# bt_remote_controller.net
KiCad netlist of a schematic drawn in EAGLE
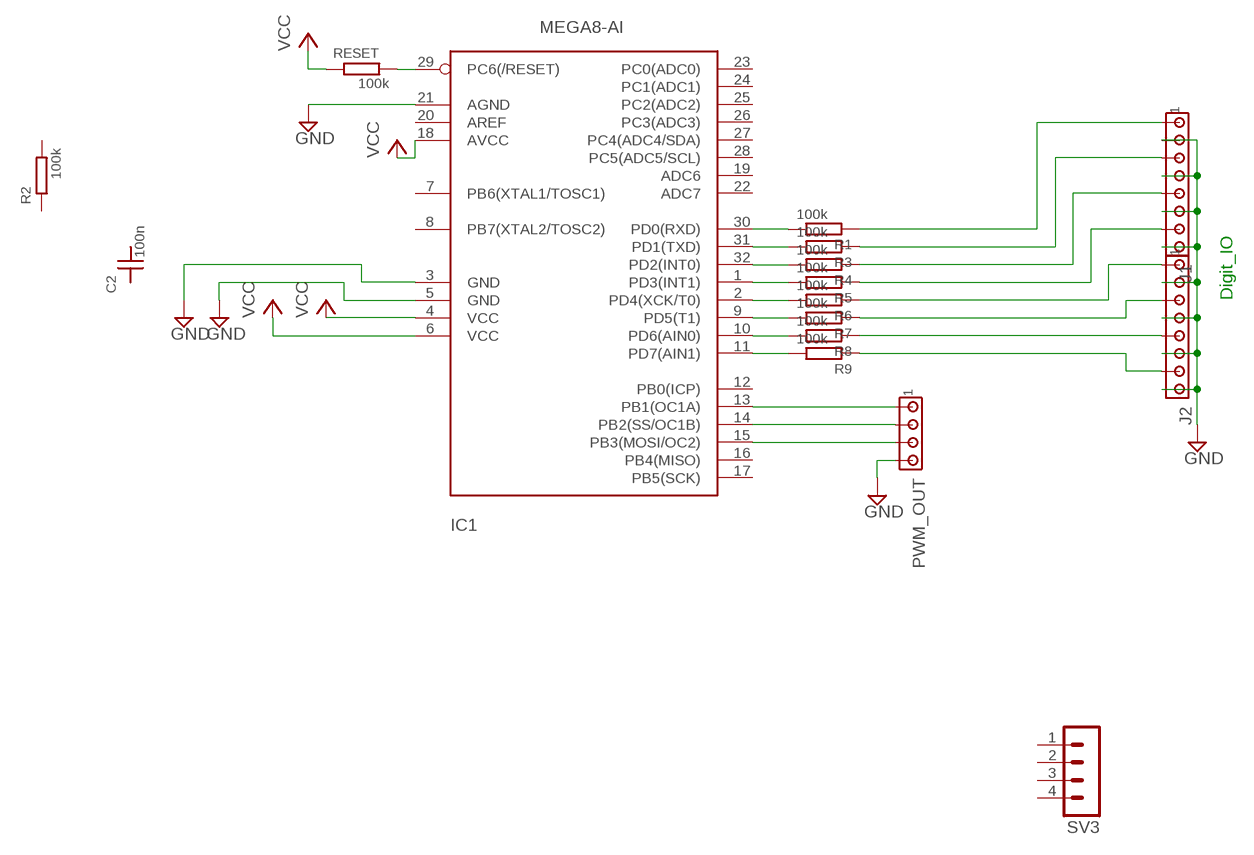
[diagram p0: schematic, sheet 1]

(export (version "E")
  (design (tool "Eeschema 10.0.6"))
  (components
    (comp (ref "C2")
      (value "100n")
      (footprint "eagle-import:1206")
      (libsource (lib "eagle-import") (part "C"))
    )
    (comp (ref "IC1")
      (value "MEGA8-AI")
      (footprint "eagle-import:TQFP32-08")
      (libsource (lib "eagle-import") (part "MEGA8-AI"))
    )
    (comp (ref "J1")
      (value "MTA08-100")
      (footprint "eagle-import:10X08MTA")
      (libsource (lib "eagle-import") (part "MTA08-100"))
    )
    (comp (ref "J2")
      (value "MTA08-100")
      (footprint "eagle-import:10X08MTA")
      (libsource (lib "eagle-import") (part "MTA08-100"))
    )
    (comp (ref "PWM_OUT")
      (value "MTA04-156")
      (footprint "eagle-import:1X4MTA")
      (libsource (lib "eagle-import") (part "MTA04-156"))
    )
    (comp (ref "R1")
      (value "100k")
      (footprint "eagle-import:1206")
      (libsource (lib "eagle-import") (part "R"))
    )
    (comp (ref "R2")
      (value "100k")
      (footprint "eagle-import:1206")
      (libsource (lib "eagle-import") (part "R"))
    )
    (comp (ref "R3")
      (value "100k")
      (footprint "eagle-import:1206")
      (libsource (lib "eagle-import") (part "R"))
    )
    (comp (ref "R4")
      (value "100k")
      (footprint "eagle-import:1206")
      (libsource (lib "eagle-import") (part "R"))
    )
    (comp (ref "R5")
      (value "100k")
      (footprint "eagle-import:1206")
      (libsource (lib "eagle-import") (part "R"))
    )
    (comp (ref "R6")
      (value "100k")
      (footprint "eagle-import:1206")
      (libsource (lib "eagle-import") (part "R"))
    )
    (comp (ref "R7")
      (value "100k")
      (footprint "eagle-import:1206")
      (libsource (lib "eagle-import") (part "R"))
    )
    (comp (ref "R8")
      (value "100k")
      (footprint "eagle-import:1206")
      (libsource (lib "eagle-import") (part "R"))
    )
    (comp (ref "R9")
      (value "100k")
      (footprint "eagle-import:1206")
      (libsource (lib "eagle-import") (part "R"))
    )
    (comp (ref "RESET")
      (value "100k")
      (footprint "eagle-import:1206")
      (libsource (lib "eagle-import") (part "R"))
    )
    (comp (ref "SV3")
      (value "MA04-1")
      (footprint "eagle-import:MA04-1")
      (libsource (lib "eagle-import") (part "MA04-1"))
    )
  )
  (nets
    (net (code "1") (name "GND") (class "Default")
      (node (ref "IC1") (pin "21") (pinfunction "AGND_21") (pintype "bidirectional"))
      (node (ref "IC1") (pin "3") (pinfunction "GND_3") (pintype "bidirectional"))
      (node (ref "IC1") (pin "5") (pinfunction "GND_5") (pintype "bidirectional"))
      (node (ref "J1") (pin "2") (pinfunction "2_2") (pintype "passive"))
      (node (ref "J1") (pin "4") (pinfunction "4_4") (pintype "passive"))
      (node (ref "J1") (pin "6") (pinfunction "6_6") (pintype "passive"))
      (node (ref "J1") (pin "8") (pinfunction "8_8") (pintype "passive"))
      (node (ref "J2") (pin "2") (pinfunction "2_2") (pintype "passive"))
      (node (ref "J2") (pin "4") (pinfunction "4_4") (pintype "passive"))
      (node (ref "J2") (pin "6") (pinfunction "6_6") (pintype "passive"))
      (node (ref "J2") (pin "8") (pinfunction "8_8") (pintype "passive"))
      (node (ref "PWM_OUT") (pin "4") (pinfunction "4_4") (pintype "passive"))
    )
    (net (code "2") (name "Net-(IC1-PB1(OC1A))") (class "Default")
      (node (ref "IC1") (pin "13") (pinfunction "PB1(OC1A)_13") (pintype "bidirectional"))
      (node (ref "PWM_OUT") (pin "1") (pinfunction "1_1") (pintype "passive"))
    )
    (net (code "3") (name "Net-(IC1-PB2(SS{slash}OC1B))") (class "Default")
      (node (ref "IC1") (pin "14") (pinfunction "PB2(SS/OC1B)_14") (pintype "bidirectional"))
      (node (ref "PWM_OUT") (pin "2") (pinfunction "2_2") (pintype "passive"))
    )
    (net (code "4") (name "Net-(IC1-PB3(MOSI{slash}OC2))") (class "Default")
      (node (ref "IC1") (pin "15") (pinfunction "PB3(MOSI/OC2)_15") (pintype "bidirectional"))
      (node (ref "PWM_OUT") (pin "3") (pinfunction "3_3") (pintype "passive"))
    )
    (net (code "5") (name "Net-(IC1-PC6({slash}RESET))") (class "Default")
      (node (ref "IC1") (pin "29") (pinfunction "PC6(/RESET)_29") (pintype "bidirectional"))
      (node (ref "RESET") (pin "PIN+") (pinfunction "P$2_PIN+") (pintype "passive"))
    )
    (net (code "6") (name "Net-(IC1-PD0(RXD))") (class "Default")
      (node (ref "IC1") (pin "30") (pinfunction "PD0(RXD)_30") (pintype "bidirectional"))
      (node (ref "R1") (pin "PIN+") (pinfunction "P$2_PIN+") (pintype "passive"))
    )
    (net (code "7") (name "Net-(IC1-PD1(TXD))") (class "Default")
      (node (ref "IC1") (pin "31") (pinfunction "PD1(TXD)_31") (pintype "bidirectional"))
      (node (ref "R3") (pin "PIN+") (pinfunction "P$2_PIN+") (pintype "passive"))
    )
    (net (code "8") (name "Net-(IC1-PD2(INT0))") (class "Default")
      (node (ref "IC1") (pin "32") (pinfunction "PD2(INT0)_32") (pintype "bidirectional"))
      (node (ref "R4") (pin "PIN+") (pinfunction "P$2_PIN+") (pintype "passive"))
    )
    (net (code "9") (name "Net-(IC1-PD3(INT1))") (class "Default")
      (node (ref "IC1") (pin "1") (pinfunction "PD3(INT1)_1") (pintype "bidirectional"))
      (node (ref "R5") (pin "PIN+") (pinfunction "P$2_PIN+") (pintype "passive"))
    )
    (net (code "10") (name "Net-(IC1-PD4(XCK{slash}T0))") (class "Default")
      (node (ref "IC1") (pin "2") (pinfunction "PD4(XCK/T0)_2") (pintype "bidirectional"))
      (node (ref "R6") (pin "PIN+") (pinfunction "P$2_PIN+") (pintype "passive"))
    )
    (net (code "11") (name "Net-(IC1-PD5(T1))") (class "Default")
      (node (ref "IC1") (pin "9") (pinfunction "PD5(T1)_9") (pintype "bidirectional"))
      (node (ref "R7") (pin "PIN+") (pinfunction "P$2_PIN+") (pintype "passive"))
    )
    (net (code "12") (name "Net-(IC1-PD6(AIN0))") (class "Default")
      (node (ref "IC1") (pin "10") (pinfunction "PD6(AIN0)_10") (pintype "bidirectional"))
      (node (ref "R8") (pin "PIN+") (pinfunction "P$2_PIN+") (pintype "passive"))
    )
    (net (code "13") (name "Net-(IC1-PD7(AIN1))") (class "Default")
      (node (ref "IC1") (pin "11") (pinfunction "PD7(AIN1)_11") (pintype "bidirectional"))
      (node (ref "R9") (pin "PIN+") (pinfunction "P$2_PIN+") (pintype "passive"))
    )
    (net (code "14") (name "Net-(R1-P$1)") (class "Default")
      (node (ref "J1") (pin "1") (pinfunction "1_1") (pintype "passive"))
      (node (ref "R1") (pin "PIN") (pinfunction "P$1_PIN") (pintype "passive"))
    )
    (net (code "15") (name "Net-(R3-P$1)") (class "Default")
      (node (ref "J1") (pin "3") (pinfunction "3_3") (pintype "passive"))
      (node (ref "R3") (pin "PIN") (pinfunction "P$1_PIN") (pintype "passive"))
    )
    (net (code "16") (name "Net-(R4-P$1)") (class "Default")
      (node (ref "J1") (pin "5") (pinfunction "5_5") (pintype "passive"))
      (node (ref "R4") (pin "PIN") (pinfunction "P$1_PIN") (pintype "passive"))
    )
    (net (code "17") (name "Net-(R5-P$1)") (class "Default")
      (node (ref "J1") (pin "7") (pinfunction "7_7") (pintype "passive"))
      (node (ref "R5") (pin "PIN") (pinfunction "P$1_PIN") (pintype "passive"))
    )
    (net (code "18") (name "Net-(R6-P$1)") (class "Default")
      (node (ref "J2") (pin "1") (pinfunction "1_1") (pintype "passive"))
      (node (ref "R6") (pin "PIN") (pinfunction "P$1_PIN") (pintype "passive"))
    )
    (net (code "19") (name "Net-(R7-P$1)") (class "Default")
      (node (ref "J2") (pin "3") (pinfunction "3_3") (pintype "passive"))
      (node (ref "R7") (pin "PIN") (pinfunction "P$1_PIN") (pintype "passive"))
    )
    (net (code "20") (name "Net-(R8-P$1)") (class "Default")
      (node (ref "J2") (pin "5") (pinfunction "5_5") (pintype "passive"))
      (node (ref "R8") (pin "PIN") (pinfunction "P$1_PIN") (pintype "passive"))
    )
    (net (code "21") (name "Net-(R9-P$1)") (class "Default")
      (node (ref "J2") (pin "7") (pinfunction "7_7") (pintype "passive"))
      (node (ref "R9") (pin "PIN") (pinfunction "P$1_PIN") (pintype "passive"))
    )
    (net (code "22") (name "VCC") (class "Default")
      (node (ref "IC1") (pin "18") (pinfunction "AVCC_18") (pintype "bidirectional"))
      (node (ref "IC1") (pin "4") (pinfunction "VCC_4") (pintype "bidirectional"))
      (node (ref "IC1") (pin "6") (pinfunction "VCC_6") (pintype "bidirectional"))
      (node (ref "RESET") (pin "PIN") (pinfunction "P$1_PIN") (pintype "passive"))
    )
    (net (code "23") (name "unconnected-(C2-P$1-PadPIN)") (class "Default")
      (node (ref "C2") (pin "PIN") (pinfunction "P$1_PIN") (pintype "passive"))
    )
    (net (code "24") (name "unconnected-(C2-P$2-PadPIN+)") (class "Default")
      (node (ref "C2") (pin "PIN+") (pinfunction "P$2_PIN+") (pintype "passive"))
    )
    (net (code "25") (name "unconnected-(IC1-ADC6-Pad19)") (class "Default")
      (node (ref "IC1") (pin "19") (pinfunction "ADC6_19") (pintype "bidirectional"))
    )
    (net (code "26") (name "unconnected-(IC1-ADC7-Pad22)") (class "Default")
      (node (ref "IC1") (pin "22") (pinfunction "ADC7_22") (pintype "bidirectional"))
    )
    (net (code "27") (name "unconnected-(IC1-AREF-Pad20)") (class "Default")
      (node (ref "IC1") (pin "20") (pinfunction "AREF_20") (pintype "bidirectional"))
    )
    (net (code "28") (name "unconnected-(IC1-PB0(ICP)-Pad12)") (class "Default")
      (node (ref "IC1") (pin "12") (pinfunction "PB0(ICP)_12") (pintype "bidirectional"))
    )
    (net (code "29") (name "unconnected-(IC1-PB4(MISO)-Pad16)") (class "Default")
      (node (ref "IC1") (pin "16") (pinfunction "PB4(MISO)_16") (pintype "bidirectional"))
    )
    (net (code "30") (name "unconnected-(IC1-PB5(SCK)-Pad17)") (class "Default")
      (node (ref "IC1") (pin "17") (pinfunction "PB5(SCK)_17") (pintype "bidirectional"))
    )
    (net (code "31") (name "unconnected-(IC1-PB6(XTAL1{slash}TOSC1)-Pad7)") (class "Default")
      (node (ref "IC1") (pin "7") (pinfunction "PB6(XTAL1/TOSC1)_7") (pintype "bidirectional"))
    )
    (net (code "32") (name "unconnected-(IC1-PB7(XTAL2{slash}TOSC2)-Pad8)") (class "Default")
      (node (ref "IC1") (pin "8") (pinfunction "PB7(XTAL2/TOSC2)_8") (pintype "bidirectional"))
    )
    (net (code "33") (name "unconnected-(IC1-PC0(ADC0)-Pad23)") (class "Default")
      (node (ref "IC1") (pin "23") (pinfunction "PC0(ADC0)_23") (pintype "bidirectional"))
    )
    (net (code "34") (name "unconnected-(IC1-PC1(ADC1)-Pad24)") (class "Default")
      (node (ref "IC1") (pin "24") (pinfunction "PC1(ADC1)_24") (pintype "bidirectional"))
    )
    (net (code "35") (name "unconnected-(IC1-PC2(ADC2)-Pad25)") (class "Default")
      (node (ref "IC1") (pin "25") (pinfunction "PC2(ADC2)_25") (pintype "bidirectional"))
    )
    (net (code "36") (name "unconnected-(IC1-PC3(ADC3)-Pad26)") (class "Default")
      (node (ref "IC1") (pin "26") (pinfunction "PC3(ADC3)_26") (pintype "bidirectional"))
    )
    (net (code "37") (name "unconnected-(IC1-PC4(ADC4{slash}SDA)-Pad27)") (class "Default")
      (node (ref "IC1") (pin "27") (pinfunction "PC4(ADC4/SDA)_27") (pintype "bidirectional"))
    )
    (net (code "38") (name "unconnected-(IC1-PC5(ADC5{slash}SCL)-Pad28)") (class "Default")
      (node (ref "IC1") (pin "28") (pinfunction "PC5(ADC5/SCL)_28") (pintype "bidirectional"))
    )
    (net (code "39") (name "unconnected-(R2-P$1-PadPIN)") (class "Default")
      (node (ref "R2") (pin "PIN") (pinfunction "P$1_PIN") (pintype "passive"))
    )
    (net (code "40") (name "unconnected-(R2-P$2-PadPIN+)") (class "Default")
      (node (ref "R2") (pin "PIN+") (pinfunction "P$2_PIN+") (pintype "passive"))
    )
    (net (code "41") (name "unconnected-(SV3-Pad1)") (class "Default")
      (node (ref "SV3") (pin "1") (pinfunction "1_1") (pintype "passive"))
    )
    (net (code "42") (name "unconnected-(SV3-Pad2)") (class "Default")
      (node (ref "SV3") (pin "2") (pinfunction "2_2") (pintype "passive"))
    )
    (net (code "43") (name "unconnected-(SV3-Pad3)") (class "Default")
      (node (ref "SV3") (pin "3") (pinfunction "3_3") (pintype "passive"))
    )
    (net (code "44") (name "unconnected-(SV3-Pad4)") (class "Default")
      (node (ref "SV3") (pin "4") (pinfunction "4_4") (pintype "passive"))
    )
  )
)
